# LPC1768_1.net
KiCad netlist of a schematic drawn in Altium Designer
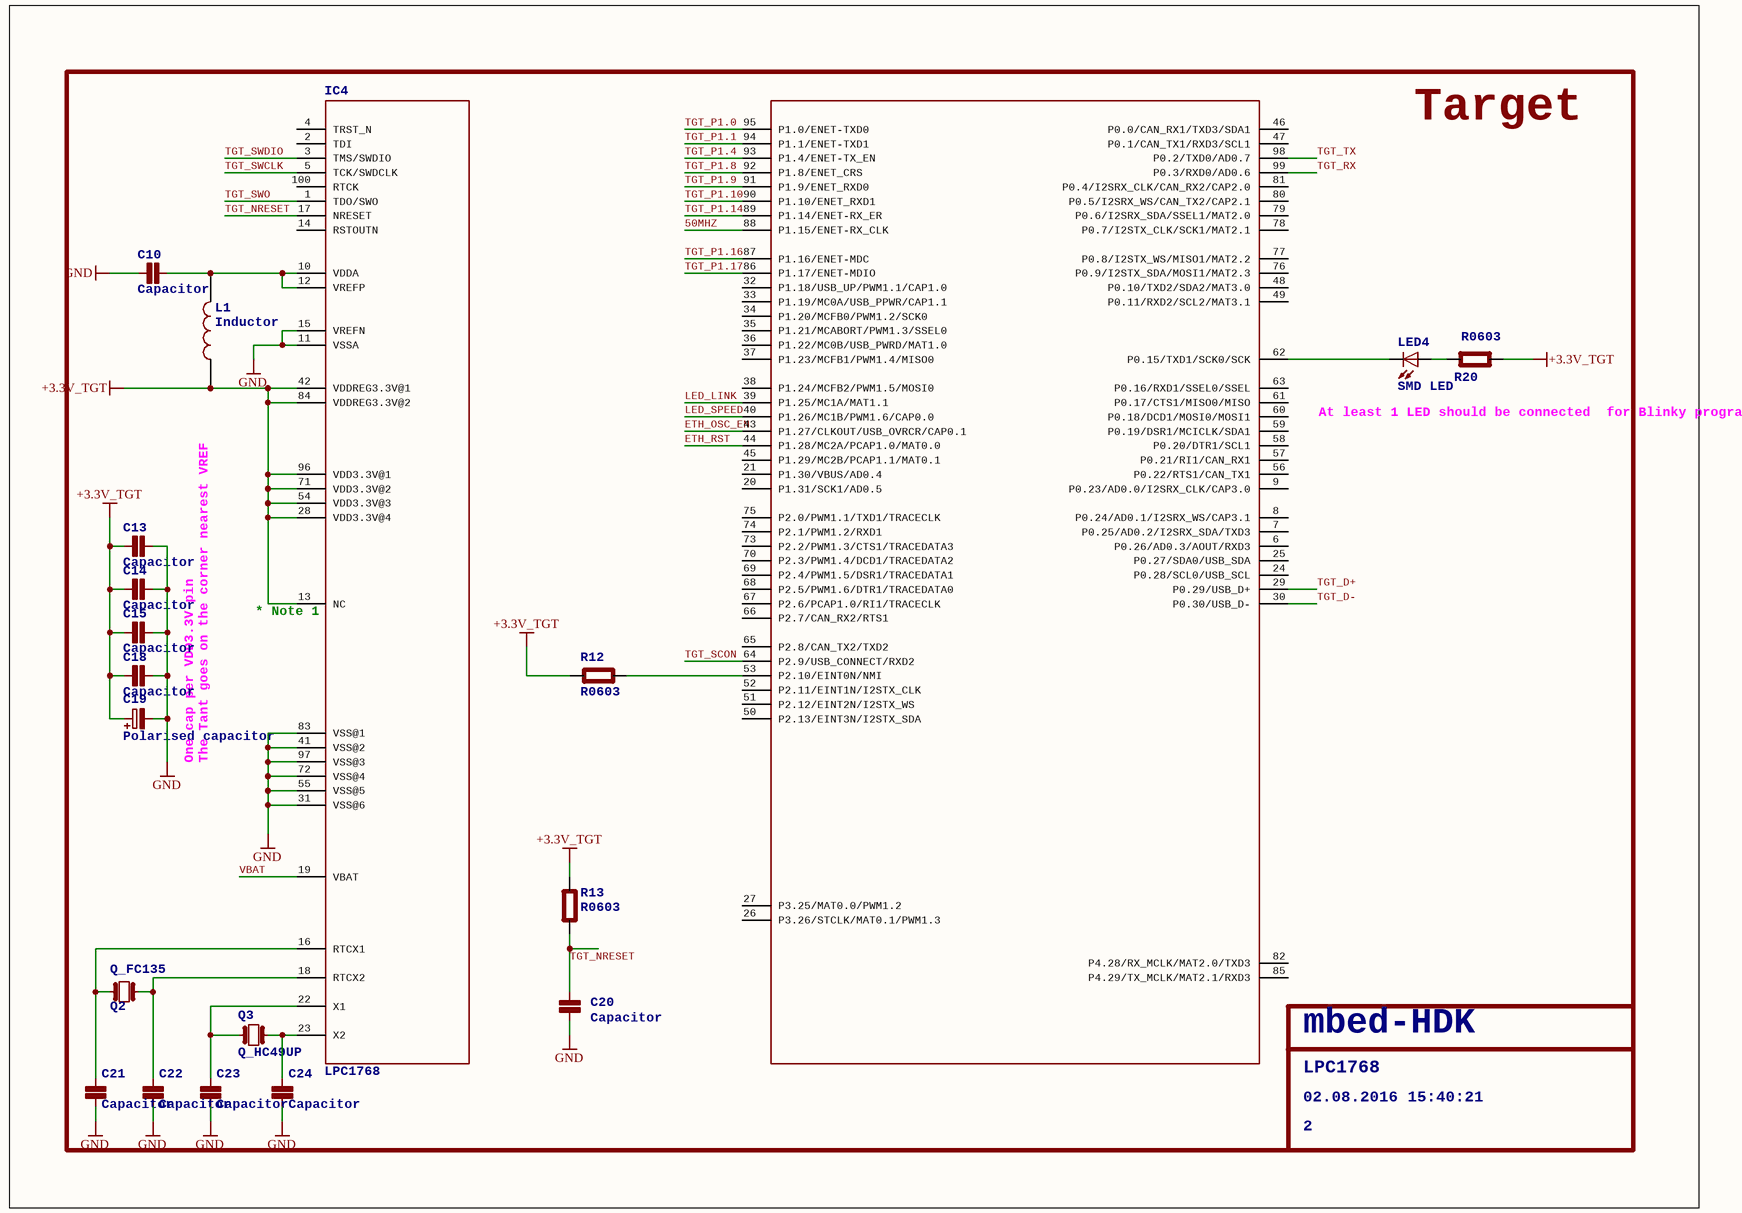
[diagram p0: LPC1768_1.SchDoc]

(export (version "E")
  (design (tool "Eeschema 10.0.6"))
  (components
    (comp (ref "C10") (value "Capacitor") (footprint "0603") (libsource (lib "") (part "C0603_2")))
    (comp (ref "C13") (value "Capacitor") (footprint "0603") (libsource (lib "") (part "C0603_1")))
    (comp (ref "C14") (value "Capacitor") (footprint "0603") (libsource (lib "") (part "C0603_1")))
    (comp (ref "C15") (value "Capacitor") (footprint "0603") (libsource (lib "") (part "C0603_1")))
    (comp (ref "C18") (value "Capacitor") (footprint "0603") (libsource (lib "") (part "C0603_1")))
    (comp (ref "C19")
      (value "Polarised capacitor")
      (footprint "CASE-B")
      (libsource (lib "mbed-HDK") (part "C-POLB"))
    )
    (comp (ref "C20") (value "Capacitor") (footprint "0603") (libsource (lib "mbed-HDK") (part "C0603")))
    (comp (ref "C21") (value "Capacitor") (footprint "0603") (libsource (lib "mbed-HDK") (part "C0603")))
    (comp (ref "C22") (value "Capacitor") (footprint "0603") (libsource (lib "mbed-HDK") (part "C0603")))
    (comp (ref "C23") (value "Capacitor") (footprint "0603") (libsource (lib "mbed-HDK") (part "C0603")))
    (comp (ref "C24") (value "Capacitor") (footprint "0603") (libsource (lib "mbed-HDK") (part "C0603")))
    (comp (ref "IC4") (value "LPC1768") (footprint "LQFP100") (libsource (lib "mbed-HDK") (part "LPC1768")))
    (comp (ref "L1") (value "Inductor") (footprint "0603") (libsource (lib "mbed-HDK") (part "L")))
    (comp (ref "LED4")
      (value "SMD LED")
      (footprint "CHIPLED_0603")
      (libsource (lib "mbed-HDK") (part "LED0603"))
    )
    (comp (ref "Q2") (value "Q_FC135") (footprint "FC135") (libsource (lib "mbed-HDK") (part "Q_FC135")))
    (comp (ref "Q3") (value "Q_HC49UP") (footprint "HC49UP") (libsource (lib "mbed-HDK") (part "Q_HC49UP")))
    (comp (ref "R12") (value "R0603") (footprint "0603") (libsource (lib "mbed-HDK") (part "R0603")))
    (comp (ref "R13") (value "R0603") (footprint "0603") (libsource (lib "mbed-HDK") (part "R0603")))
    (comp (ref "R20") (value "R0603") (footprint "0603") (libsource (lib "mbed-HDK") (part "R0603")))
  )
  (nets
    (net (code "1") (name "+3.3V_TGT") (class "Default")
      (node (ref "C13") (pin "1") (pinfunction "P$1_1") (pintype "passive"))
      (node (ref "C14") (pin "1") (pinfunction "P$1_1") (pintype "passive"))
      (node (ref "C15") (pin "1") (pinfunction "P$1_1") (pintype "passive"))
      (node (ref "C18") (pin "1") (pinfunction "P$1_1") (pintype "passive"))
      (node (ref "C19") (pin "1") (pinfunction "1_1") (pintype "passive"))
      (node (ref "IC4") (pin "13") (pinfunction "NC_13") (pintype "passive"))
      (node (ref "IC4") (pin "28") (pinfunction "VDD3.3V@4_28") (pintype "passive"))
      (node (ref "IC4") (pin "42") (pinfunction "VDDREG3.3V@1_42") (pintype "passive"))
      (node (ref "IC4") (pin "54") (pinfunction "VDD3.3V@3_54") (pintype "passive"))
      (node (ref "IC4") (pin "71") (pinfunction "VDD3.3V@2_71") (pintype "passive"))
      (node (ref "IC4") (pin "84") (pinfunction "VDDREG3.3V@2_84") (pintype "passive"))
      (node (ref "IC4") (pin "96") (pinfunction "VDD3.3V@1_96") (pintype "passive"))
      (node (ref "L1") (pin "1") (pinfunction "P$1_1") (pintype "passive"))
      (node (ref "R12") (pin "1") (pinfunction "P$1_1") (pintype "passive"))
      (node (ref "R13") (pin "2") (pinfunction "P$2_2") (pintype "passive"))
      (node (ref "R20") (pin "1") (pinfunction "P$1_1") (pintype "passive"))
    )
    (net (code "2") (name "/50MHZ") (class "Default")
      (node (ref "IC4") (pin "88") (pinfunction "P1.15/ENET-RX_CLK_88") (pintype "passive"))
    )
    (net (code "3") (name "/ETH_OSC_EN") (class "Default")
      (node (ref "IC4") (pin "43") (pinfunction "P1.27/CLKOUT/USB_OVRCR/CAP0.1_43") (pintype "passive"))
    )
    (net (code "4") (name "/ETH_RST") (class "Default")
      (node (ref "IC4") (pin "44") (pinfunction "P1.28/MC2A/PCAP1.0/MAT0.0_44") (pintype "passive"))
    )
    (net (code "5") (name "/LED_LINK") (class "Default")
      (node (ref "IC4") (pin "39") (pinfunction "P1.25/MC1A/MAT1.1_39") (pintype "passive"))
    )
    (net (code "6") (name "/LED_SPEED") (class "Default")
      (node (ref "IC4") (pin "40") (pinfunction "P1.26/MC1B/PWM1.6/CAP0.0_40") (pintype "passive"))
    )
    (net (code "7") (name "/TGT_D+") (class "Default")
      (node (ref "IC4") (pin "29") (pinfunction "P0.29/USB_D+_29") (pintype "passive"))
    )
    (net (code "8") (name "/TGT_D-") (class "Default")
      (node (ref "IC4") (pin "30") (pinfunction "P0.30/USB_D-_30") (pintype "passive"))
    )
    (net (code "9") (name "/TGT_NRESET") (class "Default")
      (node (ref "C20") (pin "2") (pinfunction "P$2_2") (pintype "passive"))
      (node (ref "IC4") (pin "17") (pinfunction "NRESET_17") (pintype "passive"))
      (node (ref "R13") (pin "1") (pinfunction "P$1_1") (pintype "passive"))
    )
    (net (code "10") (name "/TGT_P1.0") (class "Default")
      (node (ref "IC4") (pin "95") (pinfunction "P1.0/ENET-TXD0_95") (pintype "passive"))
    )
    (net (code "11") (name "/TGT_P1.1") (class "Default")
      (node (ref "IC4") (pin "94") (pinfunction "P1.1/ENET-TXD1_94") (pintype "passive"))
    )
    (net (code "12") (name "/TGT_P1.4") (class "Default")
      (node (ref "IC4") (pin "93") (pinfunction "P1.4/ENET-TX_EN_93") (pintype "passive"))
    )
    (net (code "13") (name "/TGT_P1.8") (class "Default")
      (node (ref "IC4") (pin "92") (pinfunction "P1.8/ENET_CRS_92") (pintype "passive"))
    )
    (net (code "14") (name "/TGT_P1.9") (class "Default")
      (node (ref "IC4") (pin "91") (pinfunction "P1.9/ENET_RXD0_91") (pintype "passive"))
    )
    (net (code "15") (name "/TGT_P1.10") (class "Default")
      (node (ref "IC4") (pin "90") (pinfunction "P1.10/ENET_RXD1_90") (pintype "passive"))
    )
    (net (code "16") (name "/TGT_P1.14") (class "Default")
      (node (ref "IC4") (pin "89") (pinfunction "P1.14/ENET-RX_ER_89") (pintype "passive"))
    )
    (net (code "17") (name "/TGT_P1.16") (class "Default")
      (node (ref "IC4") (pin "87") (pinfunction "P1.16/ENET-MDC_87") (pintype "passive"))
    )
    (net (code "18") (name "/TGT_P1.17") (class "Default")
      (node (ref "IC4") (pin "86") (pinfunction "P1.17/ENET-MDIO_86") (pintype "passive"))
    )
    (net (code "19") (name "/TGT_RX") (class "Default")
      (node (ref "IC4") (pin "99") (pinfunction "P0.3/RXD0/AD0.6_99") (pintype "passive"))
    )
    (net (code "20") (name "/TGT_SCON") (class "Default")
      (node (ref "IC4") (pin "64") (pinfunction "P2.9/USB_CONNECT/RXD2_64") (pintype "passive"))
    )
    (net (code "21") (name "/TGT_SWCLK") (class "Default")
      (node (ref "IC4") (pin "5") (pinfunction "TCK/SWDCLK_5") (pintype "passive"))
    )
    (net (code "22") (name "/TGT_SWDIO") (class "Default")
      (node (ref "IC4") (pin "3") (pinfunction "TMS/SWDIO_3") (pintype "passive"))
    )
    (net (code "23") (name "/TGT_SWO") (class "Default")
      (node (ref "IC4") (pin "1") (pinfunction "TDO/SWO_1") (pintype "passive"))
    )
    (net (code "24") (name "/TGT_TX") (class "Default")
      (node (ref "IC4") (pin "98") (pinfunction "P0.2/TXD0/AD0.7_98") (pintype "passive"))
    )
    (net (code "25") (name "/VBAT") (class "Default")
      (node (ref "IC4") (pin "19") (pinfunction "VBAT_19") (pintype "passive"))
    )
    (net (code "26") (name "GND") (class "Default")
      (node (ref "C10") (pin "2") (pinfunction "P$2_2") (pintype "passive"))
      (node (ref "C13") (pin "2") (pinfunction "P$2_2") (pintype "passive"))
      (node (ref "C14") (pin "2") (pinfunction "P$2_2") (pintype "passive"))
      (node (ref "C15") (pin "2") (pinfunction "P$2_2") (pintype "passive"))
      (node (ref "C18") (pin "2") (pinfunction "P$2_2") (pintype "passive"))
      (node (ref "C19") (pin "2") (pinfunction "2_2") (pintype "passive"))
      (node (ref "C20") (pin "1") (pinfunction "P$1_1") (pintype "passive"))
      (node (ref "C21") (pin "1") (pinfunction "P$1_1") (pintype "passive"))
      (node (ref "C22") (pin "1") (pinfunction "P$1_1") (pintype "passive"))
      (node (ref "C23") (pin "1") (pinfunction "P$1_1") (pintype "passive"))
      (node (ref "C24") (pin "1") (pinfunction "P$1_1") (pintype "passive"))
      (node (ref "IC4") (pin "11") (pinfunction "VSSA_11") (pintype "passive"))
      (node (ref "IC4") (pin "15") (pinfunction "VREFN_15") (pintype "passive"))
      (node (ref "IC4") (pin "31") (pinfunction "VSS@6_31") (pintype "passive"))
      (node (ref "IC4") (pin "41") (pinfunction "VSS@2_41") (pintype "passive"))
      (node (ref "IC4") (pin "55") (pinfunction "VSS@5_55") (pintype "passive"))
      (node (ref "IC4") (pin "72") (pinfunction "VSS@4_72") (pintype "passive"))
      (node (ref "IC4") (pin "83") (pinfunction "VSS@1_83") (pintype "passive"))
      (node (ref "IC4") (pin "97") (pinfunction "VSS@3_97") (pintype "passive"))
    )
    (net (code "27") (name "Net-(C10-P$1)") (class "Default")
      (node (ref "C10") (pin "1") (pinfunction "P$1_1") (pintype "passive"))
      (node (ref "IC4") (pin "10") (pinfunction "VDDA_10") (pintype "passive"))
      (node (ref "IC4") (pin "12") (pinfunction "VREFP_12") (pintype "passive"))
      (node (ref "L1") (pin "2") (pinfunction "P$2_2") (pintype "passive"))
    )
    (net (code "28") (name "Net-(C21-P$2)") (class "Default")
      (node (ref "C21") (pin "2") (pinfunction "P$2_2") (pintype "passive"))
      (node (ref "IC4") (pin "16") (pinfunction "RTCX1_16") (pintype "passive"))
      (node (ref "Q2") (pin "X2") (pinfunction "2_X2") (pintype "passive"))
    )
    (net (code "29") (name "Net-(C22-P$2)") (class "Default")
      (node (ref "C22") (pin "2") (pinfunction "P$2_2") (pintype "passive"))
      (node (ref "IC4") (pin "18") (pinfunction "RTCX2_18") (pintype "passive"))
      (node (ref "Q2") (pin "X1") (pinfunction "1_X1") (pintype "passive"))
    )
    (net (code "30") (name "Net-(C23-P$2)") (class "Default")
      (node (ref "C23") (pin "2") (pinfunction "P$2_2") (pintype "passive"))
      (node (ref "IC4") (pin "22") (pinfunction "X1_22") (pintype "passive"))
      (node (ref "Q3") (pin "1") (pinfunction "1_1") (pintype "passive"))
    )
    (net (code "31") (name "Net-(C24-P$2)") (class "Default")
      (node (ref "C24") (pin "2") (pinfunction "P$2_2") (pintype "passive"))
      (node (ref "IC4") (pin "23") (pinfunction "X2_23") (pintype "passive"))
      (node (ref "Q3") (pin "2") (pinfunction "2_2") (pintype "passive"))
    )
    (net (code "32") (name "Net-(IC4-P0.15{slash}TXD1{slash}SCK0{slash}SCK)") (class "Default")
      (node (ref "IC4") (pin "62") (pinfunction "P0.15/TXD1/SCK0/SCK_62") (pintype "passive"))
      (node (ref "LED4") (pin "C") (pinfunction "C_C") (pintype "passive"))
    )
    (net (code "33") (name "Net-(IC4-P2.10{slash}EINT0N{slash}NMI)") (class "Default")
      (node (ref "IC4") (pin "53") (pinfunction "P2.10/EINT0N/NMI_53") (pintype "passive"))
      (node (ref "R12") (pin "2") (pinfunction "P$2_2") (pintype "passive"))
    )
    (net (code "34") (name "Net-(R20-P$2)") (class "Default")
      (node (ref "LED4") (pin "A") (pinfunction "A_A") (pintype "passive"))
      (node (ref "R20") (pin "2") (pinfunction "P$2_2") (pintype "passive"))
    )
    (net (code "35") (name "unconnected-(IC4-P0.0{slash}CAN_RX1{slash}TXD3{slash}SDA1-Pad46)") (class "Default")
      (node (ref "IC4") (pin "46") (pinfunction "P0.0/CAN_RX1/TXD3/SDA1_46") (pintype "passive"))
    )
    (net (code "36") (name "unconnected-(IC4-P0.1{slash}CAN_TX1{slash}RXD3{slash}SCL1-Pad47)") (class "Default")
      (node (ref "IC4") (pin "47") (pinfunction "P0.1/CAN_TX1/RXD3/SCL1_47") (pintype "passive"))
    )
    (net (code "37") (name "unconnected-(IC4-P0.4{slash}I2SRX_CLK{slash}CAN_RX2{slash}CAP2.0-Pad81)") (class "Default")
      (node (ref "IC4") (pin "81") (pinfunction "P0.4/I2SRX_CLK/CAN_RX2/CAP2.0_81") (pintype "passive"))
    )
    (net (code "38") (name "unconnected-(IC4-P0.5{slash}I2SRX_WS{slash}CAN_TX2{slash}CAP2.1-Pad80)") (class "Default")
      (node (ref "IC4") (pin "80") (pinfunction "P0.5/I2SRX_WS/CAN_TX2/CAP2.1_80") (pintype "passive"))
    )
    (net (code "39") (name "unconnected-(IC4-P0.6{slash}I2SRX_SDA{slash}SSEL1{slash}MAT2.0-Pad79)") (class "Default")
      (node (ref "IC4") (pin "79") (pinfunction "P0.6/I2SRX_SDA/SSEL1/MAT2.0_79") (pintype "passive"))
    )
    (net (code "40") (name "unconnected-(IC4-P0.7{slash}I2STX_CLK{slash}SCK1{slash}MAT2.1-Pad78)") (class "Default")
      (node (ref "IC4") (pin "78") (pinfunction "P0.7/I2STX_CLK/SCK1/MAT2.1_78") (pintype "passive"))
    )
    (net (code "41") (name "unconnected-(IC4-P0.8{slash}I2STX_WS{slash}MISO1{slash}MAT2.2-Pad77)") (class "Default")
      (node (ref "IC4") (pin "77") (pinfunction "P0.8/I2STX_WS/MISO1/MAT2.2_77") (pintype "passive"))
    )
    (net (code "42") (name "unconnected-(IC4-P0.9{slash}I2STX_SDA{slash}MOSI1{slash}MAT2.3-Pad76)") (class "Default")
      (node (ref "IC4") (pin "76") (pinfunction "P0.9/I2STX_SDA/MOSI1/MAT2.3_76") (pintype "passive"))
    )
    (net (code "43") (name "unconnected-(IC4-P0.10{slash}TXD2{slash}SDA2{slash}MAT3.0-Pad48)") (class "Default")
      (node (ref "IC4") (pin "48") (pinfunction "P0.10/TXD2/SDA2/MAT3.0_48") (pintype "passive"))
    )
    (net (code "44") (name "unconnected-(IC4-P0.11{slash}RXD2{slash}SCL2{slash}MAT3.1-Pad49)") (class "Default")
      (node (ref "IC4") (pin "49") (pinfunction "P0.11/RXD2/SCL2/MAT3.1_49") (pintype "passive"))
    )
    (net (code "45") (name "unconnected-(IC4-P0.16{slash}RXD1{slash}SSEL0{slash}SSEL-Pad63)") (class "Default")
      (node (ref "IC4") (pin "63") (pinfunction "P0.16/RXD1/SSEL0/SSEL_63") (pintype "passive"))
    )
    (net (code "46") (name "unconnected-(IC4-P0.17{slash}CTS1{slash}MISO0{slash}MISO-Pad61)") (class "Default")
      (node (ref "IC4") (pin "61") (pinfunction "P0.17/CTS1/MISO0/MISO_61") (pintype "passive"))
    )
    (net (code "47") (name "unconnected-(IC4-P0.18{slash}DCD1{slash}MOSI0{slash}MOSI1-Pad60)") (class "Default")
      (node (ref "IC4") (pin "60") (pinfunction "P0.18/DCD1/MOSI0/MOSI1_60") (pintype "passive"))
    )
    (net (code "48") (name "unconnected-(IC4-P0.19{slash}DSR1{slash}MCICLK{slash}SDA1-Pad59)") (class "Default")
      (node (ref "IC4") (pin "59") (pinfunction "P0.19/DSR1/MCICLK/SDA1_59") (pintype "passive"))
    )
    (net (code "49") (name "unconnected-(IC4-P0.20{slash}DTR1{slash}SCL1-Pad58)") (class "Default")
      (node (ref "IC4") (pin "58") (pinfunction "P0.20/DTR1/SCL1_58") (pintype "passive"))
    )
    (net (code "50") (name "unconnected-(IC4-P0.21{slash}RI1{slash}CAN_RX1-Pad57)") (class "Default")
      (node (ref "IC4") (pin "57") (pinfunction "P0.21/RI1/CAN_RX1_57") (pintype "passive"))
    )
    (net (code "51") (name "unconnected-(IC4-P0.22{slash}RTS1{slash}CAN_TX1-Pad56)") (class "Default")
      (node (ref "IC4") (pin "56") (pinfunction "P0.22/RTS1/CAN_TX1_56") (pintype "passive"))
    )
    (net (code "52") (name "unconnected-(IC4-P0.23{slash}AD0.0{slash}I2SRX_CLK{slash}CAP3.0-Pad9)") (class "Default")
      (node (ref "IC4") (pin "9") (pinfunction "P0.23/AD0.0/I2SRX_CLK/CAP3.0_9") (pintype "passive"))
    )
    (net (code "53") (name "unconnected-(IC4-P0.24{slash}AD0.1{slash}I2SRX_WS{slash}CAP3.1-Pad8)") (class "Default")
      (node (ref "IC4") (pin "8") (pinfunction "P0.24/AD0.1/I2SRX_WS/CAP3.1_8") (pintype "passive"))
    )
    (net (code "54") (name "unconnected-(IC4-P0.25{slash}AD0.2{slash}I2SRX_SDA{slash}TXD3-Pad7)") (class "Default")
      (node (ref "IC4") (pin "7") (pinfunction "P0.25/AD0.2/I2SRX_SDA/TXD3_7") (pintype "passive"))
    )
    (net (code "55") (name "unconnected-(IC4-P0.26{slash}AD0.3{slash}AOUT{slash}RXD3-Pad6)") (class "Default")
      (node (ref "IC4") (pin "6") (pinfunction "P0.26/AD0.3/AOUT/RXD3_6") (pintype "passive"))
    )
    (net (code "56") (name "unconnected-(IC4-P0.27{slash}SDA0{slash}USB_SDA-Pad25)") (class "Default")
      (node (ref "IC4") (pin "25") (pinfunction "P0.27/SDA0/USB_SDA_25") (pintype "passive"))
    )
    (net (code "57") (name "unconnected-(IC4-P0.28{slash}SCL0{slash}USB_SCL-Pad24)") (class "Default")
      (node (ref "IC4") (pin "24") (pinfunction "P0.28/SCL0/USB_SCL_24") (pintype "passive"))
    )
    (net (code "58") (name "unconnected-(IC4-P1.18{slash}USB_UP{slash}PWM1.1{slash}CAP1.0-Pad32)") (class "Default")
      (node (ref "IC4") (pin "32") (pinfunction "P1.18/USB_UP/PWM1.1/CAP1.0_32") (pintype "passive"))
    )
    (net (code "59") (name "unconnected-(IC4-P1.19{slash}MC0A{slash}USB_PPWR{slash}CAP1.1-Pad33)") (class "Default")
      (node (ref "IC4") (pin "33") (pinfunction "P1.19/MC0A/USB_PPWR/CAP1.1_33") (pintype "passive"))
    )
    (net (code "60") (name "unconnected-(IC4-P1.20{slash}MCFB0{slash}PWM1.2{slash}SCK0-Pad34)") (class "Default")
      (node (ref "IC4") (pin "34") (pinfunction "P1.20/MCFB0/PWM1.2/SCK0_34") (pintype "passive"))
    )
    (net (code "61") (name "unconnected-(IC4-P1.21{slash}MCABORT{slash}PWM1.3{slash}SSEL0-Pad35)") (class "Default")
      (node (ref "IC4") (pin "35") (pinfunction "P1.21/MCABORT/PWM1.3/SSEL0_35") (pintype "passive"))
    )
    (net (code "62") (name "unconnected-(IC4-P1.22{slash}MC0B{slash}USB_PWRD{slash}MAT1.0-Pad36)") (class "Default")
      (node (ref "IC4") (pin "36") (pinfunction "P1.22/MC0B/USB_PWRD/MAT1.0_36") (pintype "passive"))
    )
    (net (code "63") (name "unconnected-(IC4-P1.23{slash}MCFB1{slash}PWM1.4{slash}MISO0-Pad37)") (class "Default")
      (node (ref "IC4") (pin "37") (pinfunction "P1.23/MCFB1/PWM1.4/MISO0_37") (pintype "passive"))
    )
    (net (code "64") (name "unconnected-(IC4-P1.24{slash}MCFB2{slash}PWM1.5{slash}MOSI0-Pad38)") (class "Default")
      (node (ref "IC4") (pin "38") (pinfunction "P1.24/MCFB2/PWM1.5/MOSI0_38") (pintype "passive"))
    )
    (net (code "65") (name "unconnected-(IC4-P1.29{slash}MC2B{slash}PCAP1.1{slash}MAT0.1-Pad45)") (class "Default")
      (node (ref "IC4") (pin "45") (pinfunction "P1.29/MC2B/PCAP1.1/MAT0.1_45") (pintype "passive"))
    )
    (net (code "66") (name "unconnected-(IC4-P1.30{slash}VBUS{slash}AD0.4-Pad21)") (class "Default")
      (node (ref "IC4") (pin "21") (pinfunction "P1.30/VBUS/AD0.4_21") (pintype "passive"))
    )
    (net (code "67") (name "unconnected-(IC4-P1.31{slash}SCK1{slash}AD0.5-Pad20)") (class "Default")
      (node (ref "IC4") (pin "20") (pinfunction "P1.31/SCK1/AD0.5_20") (pintype "passive"))
    )
    (net (code "68") (name "unconnected-(IC4-P2.0{slash}PWM1.1{slash}TXD1{slash}TRACECLK-Pad75)") (class "Default")
      (node (ref "IC4") (pin "75") (pinfunction "P2.0/PWM1.1/TXD1/TRACECLK_75") (pintype "passive"))
    )
    (net (code "69") (name "unconnected-(IC4-P2.1{slash}PWM1.2{slash}RXD1-Pad74)") (class "Default")
      (node (ref "IC4") (pin "74") (pinfunction "P2.1/PWM1.2/RXD1_74") (pintype "passive"))
    )
    (net (code "70") (name "unconnected-(IC4-P2.2{slash}PWM1.3{slash}CTS1{slash}TRACEDATA3-Pad73)") (class "Default")
      (node (ref "IC4") (pin "73") (pinfunction "P2.2/PWM1.3/CTS1/TRACEDATA3_73") (pintype "passive"))
    )
    (net (code "71") (name "unconnected-(IC4-P2.3{slash}PWM1.4{slash}DCD1{slash}TRACEDATA2-Pad70)") (class "Default")
      (node (ref "IC4") (pin "70") (pinfunction "P2.3/PWM1.4/DCD1/TRACEDATA2_70") (pintype "passive"))
    )
    (net (code "72") (name "unconnected-(IC4-P2.4{slash}PWM1.5{slash}DSR1{slash}TRACEDATA1-Pad69)") (class "Default")
      (node (ref "IC4") (pin "69") (pinfunction "P2.4/PWM1.5/DSR1/TRACEDATA1_69") (pintype "passive"))
    )
    (net (code "73") (name "unconnected-(IC4-P2.5{slash}PWM1.6{slash}DTR1{slash}TRACEDATA0-Pad68)") (class "Default")
      (node (ref "IC4") (pin "68") (pinfunction "P2.5/PWM1.6/DTR1/TRACEDATA0_68") (pintype "passive"))
    )
    (net (code "74") (name "unconnected-(IC4-P2.6{slash}PCAP1.0{slash}RI1{slash}TRACECLK-Pad67)") (class "Default")
      (node (ref "IC4") (pin "67") (pinfunction "P2.6/PCAP1.0/RI1/TRACECLK_67") (pintype "passive"))
    )
    (net (code "75") (name "unconnected-(IC4-P2.7{slash}CAN_RX2{slash}RTS1-Pad66)") (class "Default")
      (node (ref "IC4") (pin "66") (pinfunction "P2.7/CAN_RX2/RTS1_66") (pintype "passive"))
    )
    (net (code "76") (name "unconnected-(IC4-P2.8{slash}CAN_TX2{slash}TXD2-Pad65)") (class "Default")
      (node (ref "IC4") (pin "65") (pinfunction "P2.8/CAN_TX2/TXD2_65") (pintype "passive"))
    )
    (net (code "77") (name "unconnected-(IC4-P2.11{slash}EINT1N{slash}I2STX_CLK-Pad52)") (class "Default")
      (node (ref "IC4") (pin "52") (pinfunction "P2.11/EINT1N/I2STX_CLK_52") (pintype "passive"))
    )
    (net (code "78") (name "unconnected-(IC4-P2.12{slash}EINT2N{slash}I2STX_WS-Pad51)") (class "Default")
      (node (ref "IC4") (pin "51") (pinfunction "P2.12/EINT2N/I2STX_WS_51") (pintype "passive"))
    )
    (net (code "79") (name "unconnected-(IC4-P2.13{slash}EINT3N{slash}I2STX_SDA-Pad50)") (class "Default")
      (node (ref "IC4") (pin "50") (pinfunction "P2.13/EINT3N/I2STX_SDA_50") (pintype "passive"))
    )
    (net (code "80") (name "unconnected-(IC4-P3.25{slash}MAT0.0{slash}PWM1.2-Pad27)") (class "Default")
      (node (ref "IC4") (pin "27") (pinfunction "P3.25/MAT0.0/PWM1.2_27") (pintype "passive"))
    )
    (net (code "81") (name "unconnected-(IC4-P3.26{slash}STCLK{slash}MAT0.1{slash}PWM1.3-Pad26)") (class "Default")
      (node (ref "IC4") (pin "26") (pinfunction "P3.26/STCLK/MAT0.1/PWM1.3_26") (pintype "passive"))
    )
    (net (code "82") (name "unconnected-(IC4-P4.28{slash}RX_MCLK{slash}MAT2.0{slash}TXD3-Pad82)") (class "Default")
      (node (ref "IC4") (pin "82") (pinfunction "P4.28/RX_MCLK/MAT2.0/TXD3_82") (pintype "passive"))
    )
    (net (code "83") (name "unconnected-(IC4-P4.29{slash}TX_MCLK{slash}MAT2.1{slash}RXD3-Pad85)") (class "Default")
      (node (ref "IC4") (pin "85") (pinfunction "P4.29/TX_MCLK/MAT2.1/RXD3_85") (pintype "passive"))
    )
    (net (code "84") (name "unconnected-(IC4-RSTOUTN-Pad14)") (class "Default")
      (node (ref "IC4") (pin "14") (pinfunction "RSTOUTN_14") (pintype "passive"))
    )
    (net (code "85") (name "unconnected-(IC4-RTCK-Pad100)") (class "Default")
      (node (ref "IC4") (pin "100") (pinfunction "RTCK_100") (pintype "passive"))
    )
    (net (code "86") (name "unconnected-(IC4-TDI-Pad2)") (class "Default")
      (node (ref "IC4") (pin "2") (pinfunction "TDI_2") (pintype "passive"))
    )
    (net (code "87") (name "unconnected-(IC4-TRST_N-Pad4)") (class "Default")
      (node (ref "IC4") (pin "4") (pinfunction "TRST_N_4") (pintype "passive"))
    )
  )
)
